# dual_vca_pnl.net
KiCad netlist of a schematic drawn in EAGLE
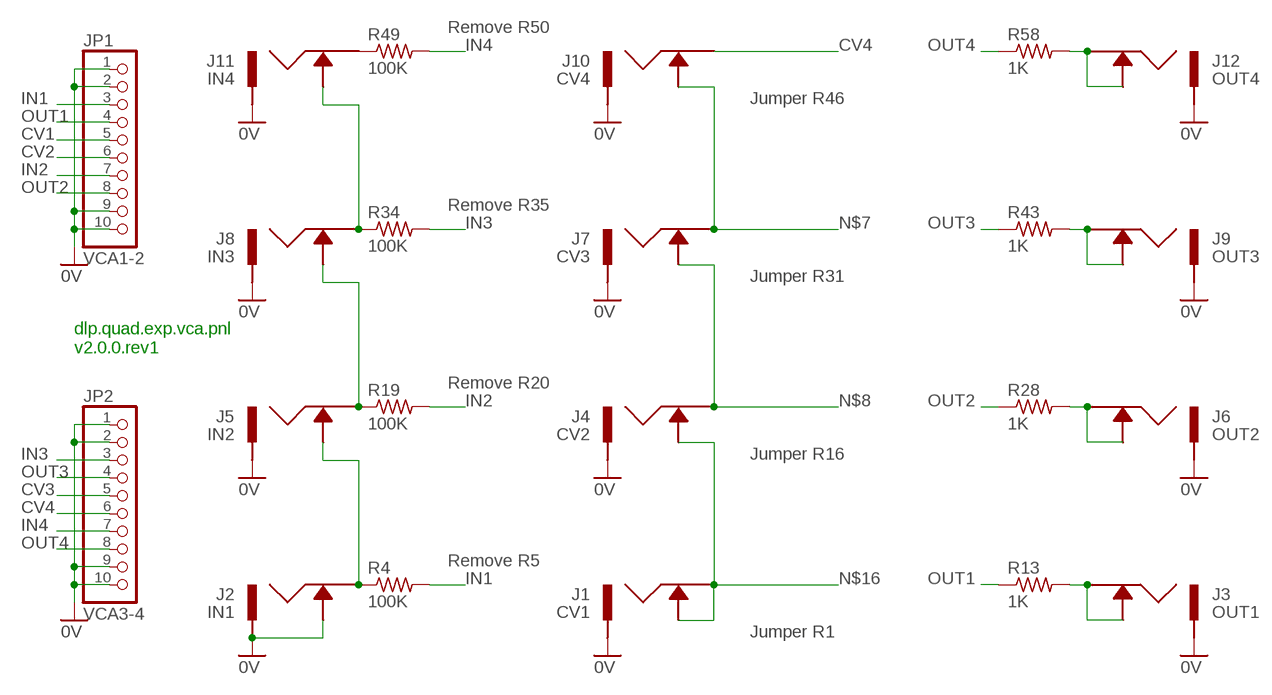
[diagram p0: schematic, sheet 1]

(export (version "E")
  (design (tool "Eeschema 10.0.6"))
  (components
    (comp (ref "J1")
      (value "CV1")
      (footprint "eagle-import:ACJM-MV35-2S")
      (libsource (lib "eagle-import") (part "ACJM-MV35-2S"))
    )
    (comp (ref "J2")
      (value "IN1")
      (footprint "eagle-import:ACJM-MV35-2S")
      (libsource (lib "eagle-import") (part "ACJM-MV35-2S"))
    )
    (comp (ref "J3")
      (value "OUT1")
      (footprint "eagle-import:ACJM-MV35-2S")
      (libsource (lib "eagle-import") (part "ACJM-MV35-2S"))
    )
    (comp (ref "J4")
      (value "CV2")
      (footprint "eagle-import:ACJM-MV35-2S")
      (libsource (lib "eagle-import") (part "ACJM-MV35-2S"))
    )
    (comp (ref "J5")
      (value "IN2")
      (footprint "eagle-import:ACJM-MV35-2S")
      (libsource (lib "eagle-import") (part "ACJM-MV35-2S"))
    )
    (comp (ref "J6")
      (value "OUT2")
      (footprint "eagle-import:ACJM-MV35-2S")
      (libsource (lib "eagle-import") (part "ACJM-MV35-2S"))
    )
    (comp (ref "J7")
      (value "CV3")
      (footprint "eagle-import:ACJM-MV35-2S")
      (libsource (lib "eagle-import") (part "ACJM-MV35-2S"))
    )
    (comp (ref "J8")
      (value "IN3")
      (footprint "eagle-import:ACJM-MV35-2S")
      (libsource (lib "eagle-import") (part "ACJM-MV35-2S"))
    )
    (comp (ref "J9")
      (value "OUT3")
      (footprint "eagle-import:ACJM-MV35-2S")
      (libsource (lib "eagle-import") (part "ACJM-MV35-2S"))
    )
    (comp (ref "J10")
      (value "CV4")
      (footprint "eagle-import:ACJM-MV35-2S")
      (libsource (lib "eagle-import") (part "ACJM-MV35-2S"))
    )
    (comp (ref "J11")
      (value "IN4")
      (footprint "eagle-import:ACJM-MV35-2S")
      (libsource (lib "eagle-import") (part "ACJM-MV35-2S"))
    )
    (comp (ref "J12")
      (value "OUT4")
      (footprint "eagle-import:ACJM-MV35-2S")
      (libsource (lib "eagle-import") (part "ACJM-MV35-2S"))
    )
    (comp (ref "JP1")
      (value "VCA1-2")
      (footprint "eagle-import:1X10")
      (libsource (lib "eagle-import") (part "PINHD-1X10"))
    )
    (comp (ref "JP2")
      (value "VCA3-4")
      (footprint "eagle-import:1X10")
      (libsource (lib "eagle-import") (part "PINHD-1X10"))
    )
    (comp (ref "R4")
      (value "100K")
      (footprint "eagle-import:0207_7")
      (libsource (lib "eagle-import") (part "R-US_0207/7"))
    )
    (comp (ref "R13")
      (value "1K")
      (footprint "eagle-import:0207_7")
      (libsource (lib "eagle-import") (part "R-US_0207/7"))
    )
    (comp (ref "R19")
      (value "100K")
      (footprint "eagle-import:0207_7")
      (libsource (lib "eagle-import") (part "R-US_0207/7"))
    )
    (comp (ref "R28")
      (value "1K")
      (footprint "eagle-import:0207_7")
      (libsource (lib "eagle-import") (part "R-US_0207/7"))
    )
    (comp (ref "R34")
      (value "100K")
      (footprint "eagle-import:0207_7")
      (libsource (lib "eagle-import") (part "R-US_0207/7"))
    )
    (comp (ref "R43")
      (value "1K")
      (footprint "eagle-import:0207_7")
      (libsource (lib "eagle-import") (part "R-US_0207/7"))
    )
    (comp (ref "R49")
      (value "100K")
      (footprint "eagle-import:0207_7")
      (libsource (lib "eagle-import") (part "R-US_0207/7"))
    )
    (comp (ref "R58")
      (value "1K")
      (footprint "eagle-import:0207_7")
      (libsource (lib "eagle-import") (part "R-US_0207/7"))
    )
  )
  (nets
    (net (code "1") (name "/CV1") (class "Default")
      (node (ref "JP1") (pin "5") (pinfunction "5_5") (pintype "passive"))
    )
    (net (code "2") (name "/CV2") (class "Default")
      (node (ref "JP1") (pin "6") (pinfunction "6_6") (pintype "passive"))
    )
    (net (code "3") (name "/CV3") (class "Default")
      (node (ref "JP2") (pin "5") (pinfunction "5_5") (pintype "passive"))
    )
    (net (code "4") (name "/CV4") (class "Default")
      (node (ref "J10") (pin "P$3") (pinfunction "P$2_P$3") (pintype "bidirectional"))
      (node (ref "JP2") (pin "6") (pinfunction "6_6") (pintype "passive"))
    )
    (net (code "5") (name "/IN1") (class "Default")
      (node (ref "JP1") (pin "3") (pinfunction "3_3") (pintype "passive"))
      (node (ref "R4") (pin "2") (pinfunction "2_2") (pintype "passive"))
    )
    (net (code "6") (name "/IN2") (class "Default")
      (node (ref "JP1") (pin "7") (pinfunction "7_7") (pintype "passive"))
      (node (ref "R19") (pin "2") (pinfunction "2_2") (pintype "passive"))
    )
    (net (code "7") (name "/IN3") (class "Default")
      (node (ref "JP2") (pin "3") (pinfunction "3_3") (pintype "passive"))
      (node (ref "R34") (pin "2") (pinfunction "2_2") (pintype "passive"))
    )
    (net (code "8") (name "/IN4") (class "Default")
      (node (ref "JP2") (pin "7") (pinfunction "7_7") (pintype "passive"))
      (node (ref "R49") (pin "2") (pinfunction "2_2") (pintype "passive"))
    )
    (net (code "9") (name "/N$7") (class "Default")
      (node (ref "J10") (pin "P$2") (pinfunction "P$3_P$2") (pintype "bidirectional"))
      (node (ref "J7") (pin "P$3") (pinfunction "P$2_P$3") (pintype "bidirectional"))
    )
    (net (code "10") (name "/N$8") (class "Default")
      (node (ref "J4") (pin "P$3") (pinfunction "P$2_P$3") (pintype "bidirectional"))
      (node (ref "J7") (pin "P$2") (pinfunction "P$3_P$2") (pintype "bidirectional"))
    )
    (net (code "11") (name "/N$16") (class "Default")
      (node (ref "J1") (pin "P$2") (pinfunction "P$3_P$2") (pintype "bidirectional"))
      (node (ref "J1") (pin "P$3") (pinfunction "P$2_P$3") (pintype "bidirectional"))
      (node (ref "J4") (pin "P$2") (pinfunction "P$3_P$2") (pintype "bidirectional"))
    )
    (net (code "12") (name "/OUT1") (class "Default")
      (node (ref "JP1") (pin "4") (pinfunction "4_4") (pintype "passive"))
      (node (ref "R13") (pin "1") (pinfunction "1_1") (pintype "passive"))
    )
    (net (code "13") (name "/OUT2") (class "Default")
      (node (ref "JP1") (pin "8") (pinfunction "8_8") (pintype "passive"))
      (node (ref "R28") (pin "1") (pinfunction "1_1") (pintype "passive"))
    )
    (net (code "14") (name "/OUT3") (class "Default")
      (node (ref "JP2") (pin "4") (pinfunction "4_4") (pintype "passive"))
      (node (ref "R43") (pin "1") (pinfunction "1_1") (pintype "passive"))
    )
    (net (code "15") (name "/OUT4") (class "Default")
      (node (ref "JP2") (pin "8") (pinfunction "8_8") (pintype "passive"))
      (node (ref "R58") (pin "1") (pinfunction "1_1") (pintype "passive"))
    )
    (net (code "16") (name "0V") (class "Default")
      (node (ref "J1") (pin "P$1") (pinfunction "P$1_P$1") (pintype "bidirectional"))
      (node (ref "J10") (pin "P$1") (pinfunction "P$1_P$1") (pintype "bidirectional"))
      (node (ref "J11") (pin "P$1") (pinfunction "P$1_P$1") (pintype "bidirectional"))
      (node (ref "J12") (pin "P$1") (pinfunction "P$1_P$1") (pintype "bidirectional"))
      (node (ref "J2") (pin "P$1") (pinfunction "P$1_P$1") (pintype "bidirectional"))
      (node (ref "J2") (pin "P$2") (pinfunction "P$3_P$2") (pintype "bidirectional"))
      (node (ref "J3") (pin "P$1") (pinfunction "P$1_P$1") (pintype "bidirectional"))
      (node (ref "J4") (pin "P$1") (pinfunction "P$1_P$1") (pintype "bidirectional"))
      (node (ref "J5") (pin "P$1") (pinfunction "P$1_P$1") (pintype "bidirectional"))
      (node (ref "J6") (pin "P$1") (pinfunction "P$1_P$1") (pintype "bidirectional"))
      (node (ref "J7") (pin "P$1") (pinfunction "P$1_P$1") (pintype "bidirectional"))
      (node (ref "J8") (pin "P$1") (pinfunction "P$1_P$1") (pintype "bidirectional"))
      (node (ref "J9") (pin "P$1") (pinfunction "P$1_P$1") (pintype "bidirectional"))
      (node (ref "JP1") (pin "1") (pinfunction "1_1") (pintype "passive"))
      (node (ref "JP1") (pin "10") (pinfunction "10_10") (pintype "passive"))
      (node (ref "JP1") (pin "2") (pinfunction "2_2") (pintype "passive"))
      (node (ref "JP1") (pin "9") (pinfunction "9_9") (pintype "passive"))
      (node (ref "JP2") (pin "1") (pinfunction "1_1") (pintype "passive"))
      (node (ref "JP2") (pin "10") (pinfunction "10_10") (pintype "passive"))
      (node (ref "JP2") (pin "2") (pinfunction "2_2") (pintype "passive"))
      (node (ref "JP2") (pin "9") (pinfunction "9_9") (pintype "passive"))
    )
    (net (code "17") (name "Net-(J2-P$2)") (class "Default")
      (node (ref "J2") (pin "P$3") (pinfunction "P$2_P$3") (pintype "bidirectional"))
      (node (ref "J5") (pin "P$2") (pinfunction "P$3_P$2") (pintype "bidirectional"))
      (node (ref "R4") (pin "1") (pinfunction "1_1") (pintype "passive"))
    )
    (net (code "18") (name "Net-(J3-P$2)") (class "Default")
      (node (ref "J3") (pin "P$2") (pinfunction "P$3_P$2") (pintype "bidirectional"))
      (node (ref "J3") (pin "P$3") (pinfunction "P$2_P$3") (pintype "bidirectional"))
      (node (ref "R13") (pin "2") (pinfunction "2_2") (pintype "passive"))
    )
    (net (code "19") (name "Net-(J5-P$2)") (class "Default")
      (node (ref "J5") (pin "P$3") (pinfunction "P$2_P$3") (pintype "bidirectional"))
      (node (ref "J8") (pin "P$2") (pinfunction "P$3_P$2") (pintype "bidirectional"))
      (node (ref "R19") (pin "1") (pinfunction "1_1") (pintype "passive"))
    )
    (net (code "20") (name "Net-(J6-P$2)") (class "Default")
      (node (ref "J6") (pin "P$2") (pinfunction "P$3_P$2") (pintype "bidirectional"))
      (node (ref "J6") (pin "P$3") (pinfunction "P$2_P$3") (pintype "bidirectional"))
      (node (ref "R28") (pin "2") (pinfunction "2_2") (pintype "passive"))
    )
    (net (code "21") (name "Net-(J9-P$2)") (class "Default")
      (node (ref "J9") (pin "P$2") (pinfunction "P$3_P$2") (pintype "bidirectional"))
      (node (ref "J9") (pin "P$3") (pinfunction "P$2_P$3") (pintype "bidirectional"))
      (node (ref "R43") (pin "2") (pinfunction "2_2") (pintype "passive"))
    )
    (net (code "22") (name "Net-(J11-P$2)") (class "Default")
      (node (ref "J11") (pin "P$3") (pinfunction "P$2_P$3") (pintype "bidirectional"))
      (node (ref "R49") (pin "1") (pinfunction "1_1") (pintype "passive"))
    )
    (net (code "23") (name "Net-(J11-P$3)") (class "Default")
      (node (ref "J11") (pin "P$2") (pinfunction "P$3_P$2") (pintype "bidirectional"))
      (node (ref "J8") (pin "P$3") (pinfunction "P$2_P$3") (pintype "bidirectional"))
      (node (ref "R34") (pin "1") (pinfunction "1_1") (pintype "passive"))
    )
    (net (code "24") (name "Net-(J12-P$2)") (class "Default")
      (node (ref "J12") (pin "P$2") (pinfunction "P$3_P$2") (pintype "bidirectional"))
      (node (ref "J12") (pin "P$3") (pinfunction "P$2_P$3") (pintype "bidirectional"))
      (node (ref "R58") (pin "2") (pinfunction "2_2") (pintype "passive"))
    )
  )
)
